# p.net
KiCad netlist of a schematic drawn in EAGLE
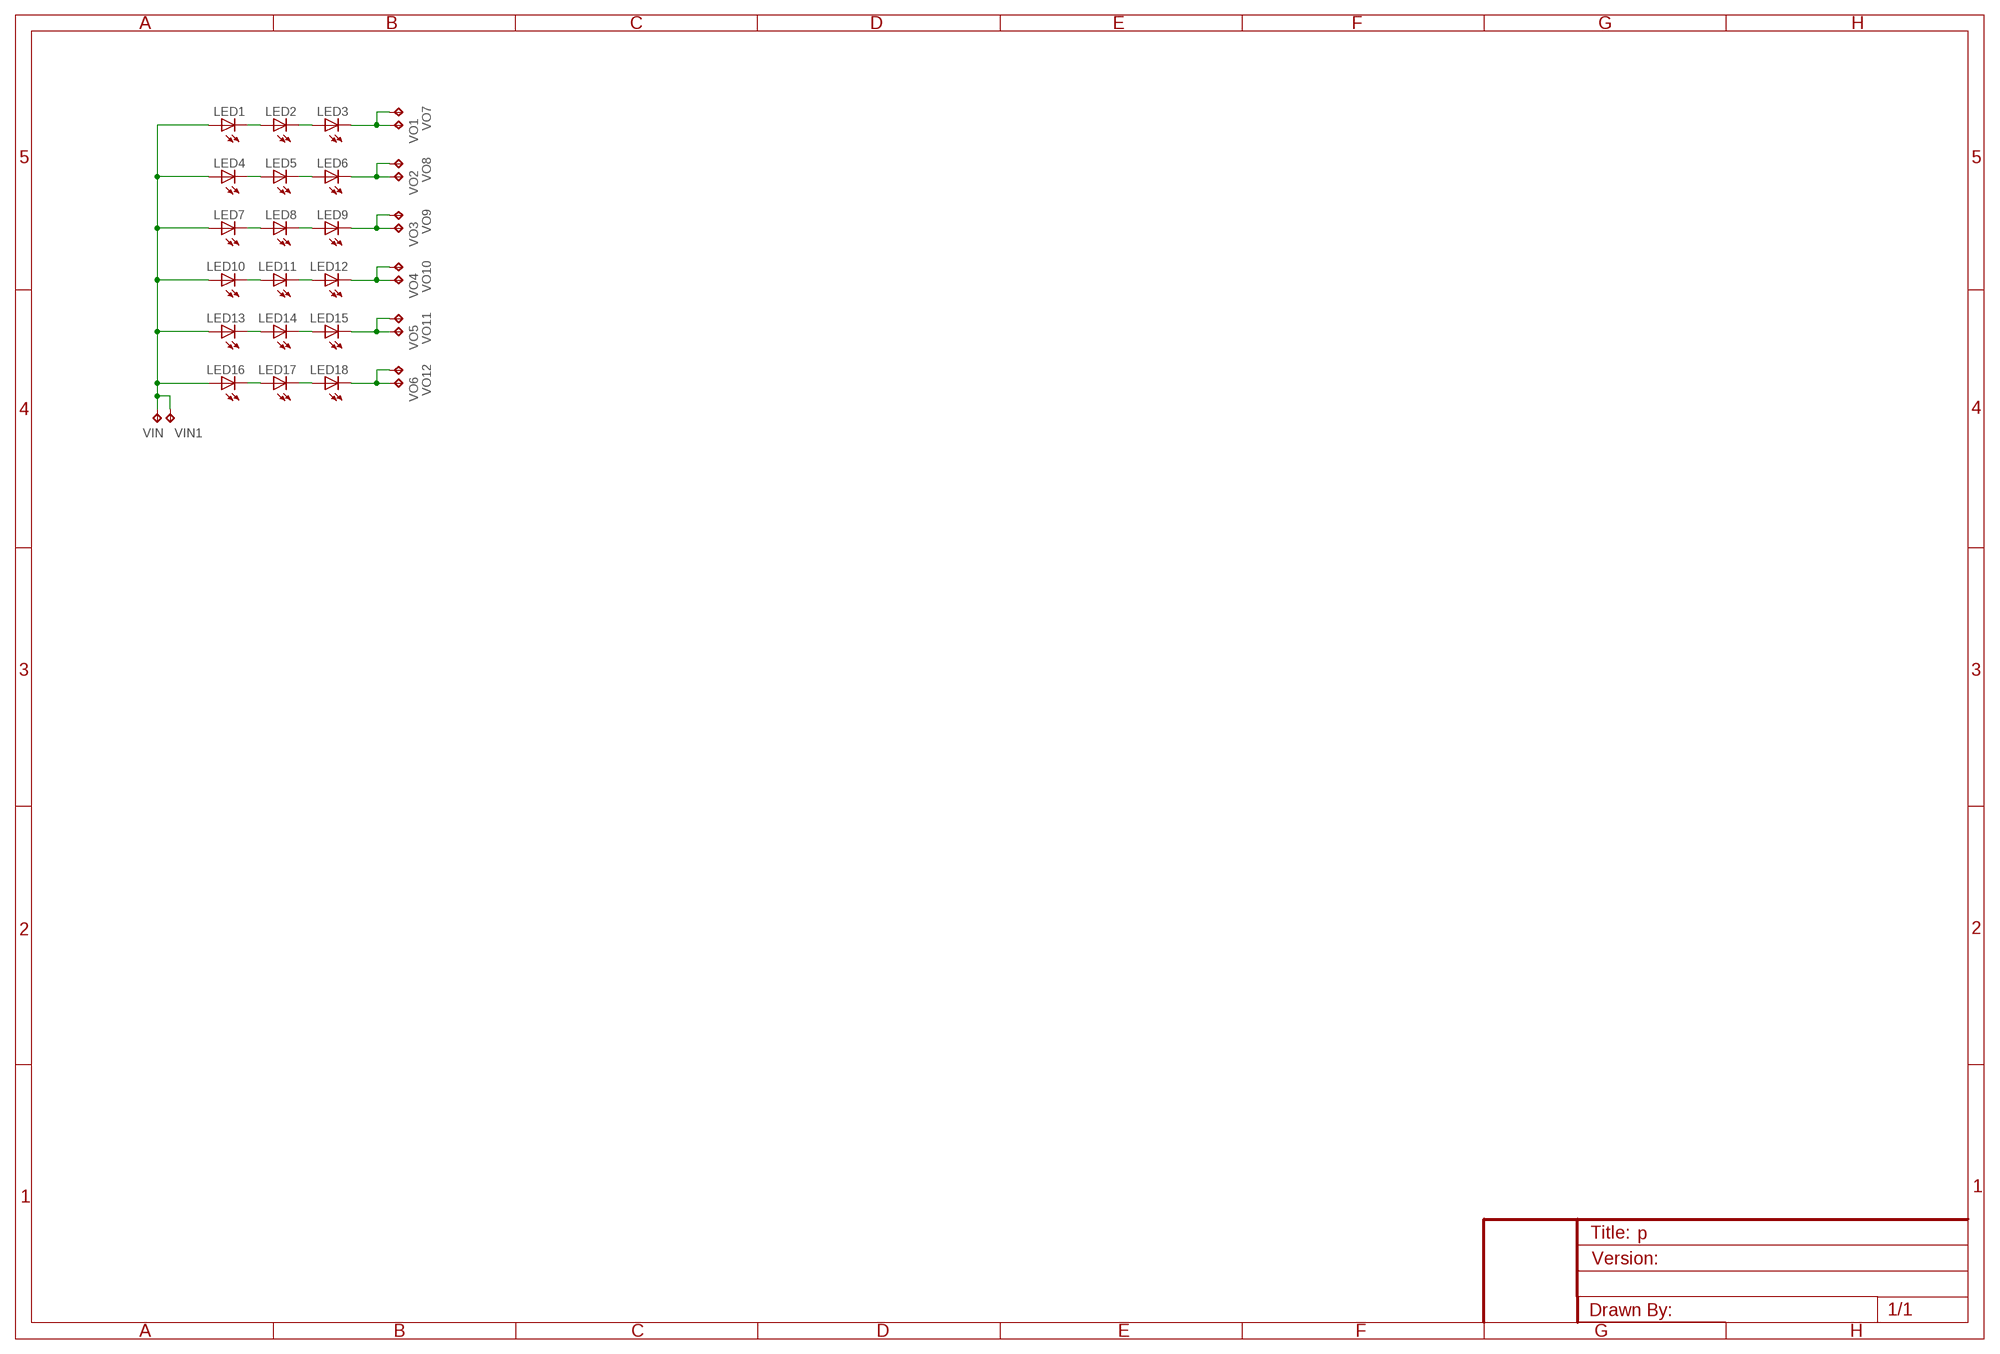
[diagram p0: schematic, sheet 1]

(export (version "E")
  (design (tool "Eeschema 10.0.6"))
  (components
    (comp (ref "LED1")
      (value "LED0805")
      (footprint "eagle-import:LED_0805")
      (libsource (lib "eagle-import") (part "LED0805"))
    )
    (comp (ref "LED2")
      (value "LED0805")
      (footprint "eagle-import:LED_0805")
      (libsource (lib "eagle-import") (part "LED0805"))
    )
    (comp (ref "LED3")
      (value "LED0805")
      (footprint "eagle-import:LED_0805")
      (libsource (lib "eagle-import") (part "LED0805"))
    )
    (comp (ref "LED4")
      (value "LED0805")
      (footprint "eagle-import:LED_0805")
      (libsource (lib "eagle-import") (part "LED0805"))
    )
    (comp (ref "LED5")
      (value "LED0805")
      (footprint "eagle-import:LED_0805")
      (libsource (lib "eagle-import") (part "LED0805"))
    )
    (comp (ref "LED6")
      (value "LED0805")
      (footprint "eagle-import:LED_0805")
      (libsource (lib "eagle-import") (part "LED0805"))
    )
    (comp (ref "LED7")
      (value "LED0805")
      (footprint "eagle-import:LED_0805")
      (libsource (lib "eagle-import") (part "LED0805"))
    )
    (comp (ref "LED8")
      (value "LED0805")
      (footprint "eagle-import:LED_0805")
      (libsource (lib "eagle-import") (part "LED0805"))
    )
    (comp (ref "LED9")
      (value "LED0805")
      (footprint "eagle-import:LED_0805")
      (libsource (lib "eagle-import") (part "LED0805"))
    )
    (comp (ref "LED10")
      (value "LED0805")
      (footprint "eagle-import:LED_0805")
      (libsource (lib "eagle-import") (part "LED0805"))
    )
    (comp (ref "LED11")
      (value "LED0805")
      (footprint "eagle-import:LED_0805")
      (libsource (lib "eagle-import") (part "LED0805"))
    )
    (comp (ref "LED12")
      (value "LED0805")
      (footprint "eagle-import:LED_0805")
      (libsource (lib "eagle-import") (part "LED0805"))
    )
    (comp (ref "LED13")
      (value "LED0805")
      (footprint "eagle-import:LED_0805")
      (libsource (lib "eagle-import") (part "LED0805"))
    )
    (comp (ref "LED14")
      (value "LED0805")
      (footprint "eagle-import:LED_0805")
      (libsource (lib "eagle-import") (part "LED0805"))
    )
    (comp (ref "LED15")
      (value "LED0805")
      (footprint "eagle-import:LED_0805")
      (libsource (lib "eagle-import") (part "LED0805"))
    )
    (comp (ref "LED16")
      (value "LED0805")
      (footprint "eagle-import:LED_0805")
      (libsource (lib "eagle-import") (part "LED0805"))
    )
    (comp (ref "LED17")
      (value "LED0805")
      (footprint "eagle-import:LED_0805")
      (libsource (lib "eagle-import") (part "LED0805"))
    )
    (comp (ref "LED18")
      (value "LED0805")
      (footprint "eagle-import:LED_0805")
      (libsource (lib "eagle-import") (part "LED0805"))
    )
    (comp (ref "VIN")
      (value "TEST_POINTPAD1-20")
      (footprint "eagle-import:P1-20")
      (libsource (lib "eagle-import") (part "TEST_POINTPAD1-20"))
    )
    (comp (ref "VIN1")
      (value "TEST_POINTPAD1-20")
      (footprint "eagle-import:P1-20")
      (libsource (lib "eagle-import") (part "TEST_POINTPAD1-20"))
    )
    (comp (ref "VO1")
      (value "TEST_POINTPAD1-20")
      (footprint "eagle-import:P1-20")
      (libsource (lib "eagle-import") (part "TEST_POINTPAD1-20"))
    )
    (comp (ref "VO2")
      (value "TEST_POINTPAD1-20")
      (footprint "eagle-import:P1-20")
      (libsource (lib "eagle-import") (part "TEST_POINTPAD1-20"))
    )
    (comp (ref "VO3")
      (value "TEST_POINTPAD1-20")
      (footprint "eagle-import:P1-20")
      (libsource (lib "eagle-import") (part "TEST_POINTPAD1-20"))
    )
    (comp (ref "VO4")
      (value "TEST_POINTPAD1-20")
      (footprint "eagle-import:P1-20")
      (libsource (lib "eagle-import") (part "TEST_POINTPAD1-20"))
    )
    (comp (ref "VO5")
      (value "TEST_POINTPAD1-20")
      (footprint "eagle-import:P1-20")
      (libsource (lib "eagle-import") (part "TEST_POINTPAD1-20"))
    )
    (comp (ref "VO6")
      (value "TEST_POINTPAD1-20")
      (footprint "eagle-import:P1-20")
      (libsource (lib "eagle-import") (part "TEST_POINTPAD1-20"))
    )
    (comp (ref "VO7")
      (value "TEST_POINTPAD1-20")
      (footprint "eagle-import:P1-20")
      (libsource (lib "eagle-import") (part "TEST_POINTPAD1-20"))
    )
    (comp (ref "VO8")
      (value "TEST_POINTPAD1-20")
      (footprint "eagle-import:P1-20")
      (libsource (lib "eagle-import") (part "TEST_POINTPAD1-20"))
    )
    (comp (ref "VO9")
      (value "TEST_POINTPAD1-20")
      (footprint "eagle-import:P1-20")
      (libsource (lib "eagle-import") (part "TEST_POINTPAD1-20"))
    )
    (comp (ref "VO10")
      (value "TEST_POINTPAD1-20")
      (footprint "eagle-import:P1-20")
      (libsource (lib "eagle-import") (part "TEST_POINTPAD1-20"))
    )
    (comp (ref "VO11")
      (value "TEST_POINTPAD1-20")
      (footprint "eagle-import:P1-20")
      (libsource (lib "eagle-import") (part "TEST_POINTPAD1-20"))
    )
    (comp (ref "VO12")
      (value "TEST_POINTPAD1-20")
      (footprint "eagle-import:P1-20")
      (libsource (lib "eagle-import") (part "TEST_POINTPAD1-20"))
    )
  )
  (nets
    (net (code "1") (name "Net-(LED1-PadA)") (class "Default")
      (node (ref "LED1") (pin "A") (pinfunction "A_A") (pintype "passive"))
      (node (ref "LED10") (pin "A") (pinfunction "A_A") (pintype "passive"))
      (node (ref "LED13") (pin "A") (pinfunction "A_A") (pintype "passive"))
      (node (ref "LED16") (pin "A") (pinfunction "A_A") (pintype "passive"))
      (node (ref "LED4") (pin "A") (pinfunction "A_A") (pintype "passive"))
      (node (ref "LED7") (pin "A") (pinfunction "A_A") (pintype "passive"))
      (node (ref "VIN") (pin "TP") (pinfunction "TP_TP") (pintype "input"))
      (node (ref "VIN1") (pin "TP") (pinfunction "TP_TP") (pintype "input"))
    )
    (net (code "2") (name "Net-(LED1-PadC)") (class "Default")
      (node (ref "LED1") (pin "C") (pinfunction "C_C") (pintype "passive"))
      (node (ref "LED2") (pin "A") (pinfunction "A_A") (pintype "passive"))
    )
    (net (code "3") (name "Net-(LED2-PadC)") (class "Default")
      (node (ref "LED2") (pin "C") (pinfunction "C_C") (pintype "passive"))
      (node (ref "LED3") (pin "A") (pinfunction "A_A") (pintype "passive"))
    )
    (net (code "4") (name "Net-(LED3-PadC)") (class "Default")
      (node (ref "LED3") (pin "C") (pinfunction "C_C") (pintype "passive"))
      (node (ref "VO1") (pin "TP") (pinfunction "TP_TP") (pintype "input"))
      (node (ref "VO7") (pin "TP") (pinfunction "TP_TP") (pintype "input"))
    )
    (net (code "5") (name "Net-(LED4-PadC)") (class "Default")
      (node (ref "LED4") (pin "C") (pinfunction "C_C") (pintype "passive"))
      (node (ref "LED5") (pin "A") (pinfunction "A_A") (pintype "passive"))
    )
    (net (code "6") (name "Net-(LED5-PadC)") (class "Default")
      (node (ref "LED5") (pin "C") (pinfunction "C_C") (pintype "passive"))
      (node (ref "LED6") (pin "A") (pinfunction "A_A") (pintype "passive"))
    )
    (net (code "7") (name "Net-(LED6-PadC)") (class "Default")
      (node (ref "LED6") (pin "C") (pinfunction "C_C") (pintype "passive"))
      (node (ref "VO2") (pin "TP") (pinfunction "TP_TP") (pintype "input"))
      (node (ref "VO8") (pin "TP") (pinfunction "TP_TP") (pintype "input"))
    )
    (net (code "8") (name "Net-(LED7-PadC)") (class "Default")
      (node (ref "LED7") (pin "C") (pinfunction "C_C") (pintype "passive"))
      (node (ref "LED8") (pin "A") (pinfunction "A_A") (pintype "passive"))
    )
    (net (code "9") (name "Net-(LED8-PadC)") (class "Default")
      (node (ref "LED8") (pin "C") (pinfunction "C_C") (pintype "passive"))
      (node (ref "LED9") (pin "A") (pinfunction "A_A") (pintype "passive"))
    )
    (net (code "10") (name "Net-(LED9-PadC)") (class "Default")
      (node (ref "LED9") (pin "C") (pinfunction "C_C") (pintype "passive"))
      (node (ref "VO3") (pin "TP") (pinfunction "TP_TP") (pintype "input"))
      (node (ref "VO9") (pin "TP") (pinfunction "TP_TP") (pintype "input"))
    )
    (net (code "11") (name "Net-(LED10-PadC)") (class "Default")
      (node (ref "LED10") (pin "C") (pinfunction "C_C") (pintype "passive"))
      (node (ref "LED11") (pin "A") (pinfunction "A_A") (pintype "passive"))
    )
    (net (code "12") (name "Net-(LED11-PadC)") (class "Default")
      (node (ref "LED11") (pin "C") (pinfunction "C_C") (pintype "passive"))
      (node (ref "LED12") (pin "A") (pinfunction "A_A") (pintype "passive"))
    )
    (net (code "13") (name "Net-(LED12-PadC)") (class "Default")
      (node (ref "LED12") (pin "C") (pinfunction "C_C") (pintype "passive"))
      (node (ref "VO10") (pin "TP") (pinfunction "TP_TP") (pintype "input"))
      (node (ref "VO4") (pin "TP") (pinfunction "TP_TP") (pintype "input"))
    )
    (net (code "14") (name "Net-(LED13-PadC)") (class "Default")
      (node (ref "LED13") (pin "C") (pinfunction "C_C") (pintype "passive"))
      (node (ref "LED14") (pin "A") (pinfunction "A_A") (pintype "passive"))
    )
    (net (code "15") (name "Net-(LED14-PadC)") (class "Default")
      (node (ref "LED14") (pin "C") (pinfunction "C_C") (pintype "passive"))
      (node (ref "LED15") (pin "A") (pinfunction "A_A") (pintype "passive"))
    )
    (net (code "16") (name "Net-(LED15-PadC)") (class "Default")
      (node (ref "LED15") (pin "C") (pinfunction "C_C") (pintype "passive"))
      (node (ref "VO11") (pin "TP") (pinfunction "TP_TP") (pintype "input"))
      (node (ref "VO5") (pin "TP") (pinfunction "TP_TP") (pintype "input"))
    )
    (net (code "17") (name "Net-(LED16-PadC)") (class "Default")
      (node (ref "LED16") (pin "C") (pinfunction "C_C") (pintype "passive"))
      (node (ref "LED17") (pin "A") (pinfunction "A_A") (pintype "passive"))
    )
    (net (code "18") (name "Net-(LED17-PadC)") (class "Default")
      (node (ref "LED17") (pin "C") (pinfunction "C_C") (pintype "passive"))
      (node (ref "LED18") (pin "A") (pinfunction "A_A") (pintype "passive"))
    )
    (net (code "19") (name "Net-(LED18-PadC)") (class "Default")
      (node (ref "LED18") (pin "C") (pinfunction "C_C") (pintype "passive"))
      (node (ref "VO12") (pin "TP") (pinfunction "TP_TP") (pintype "input"))
      (node (ref "VO6") (pin "TP") (pinfunction "TP_TP") (pintype "input"))
    )
  )
)
